# SpO_Sensor.net
KiCad netlist of a schematic drawn in Altium Designer
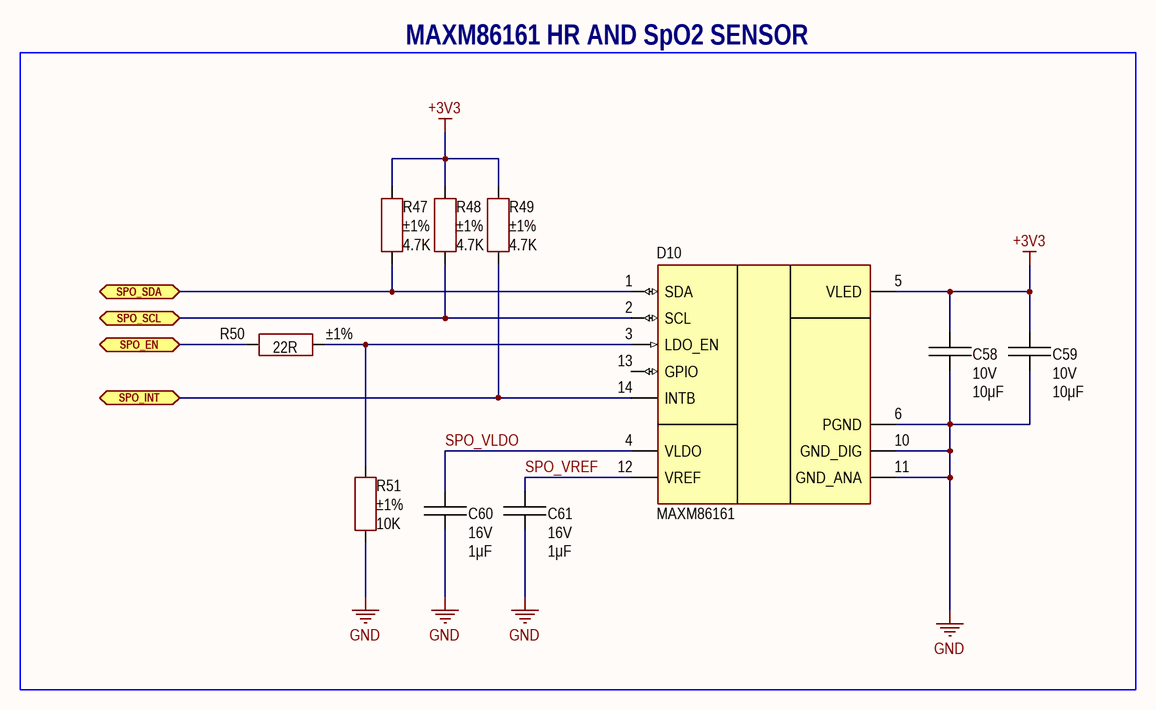
[diagram p0: SpO_Sensor.SchDoc]

(export (version "E")
  (design (tool "Eeschema 10.0.6"))
  (components
    (comp (ref "C58")
      (value "10μF")
      (footprint "CAP: 0805")
      (description "10 µF ±10% 10V Ceramic Capacitor X7R 0805 (2012 Metric)")
      (fields
        (field (name "MANUFACTURER") "Yageo")
        (field (name "PARTNUMBER") "CC0805KFX7R6BB106")
        (field (name "VOLTAGE") "10V")
      )
      (libsource (lib "capacitor") (part "Ceramic_0805"))
    )
    (comp (ref "C59")
      (value "10μF")
      (footprint "CAP: 0805")
      (description "10 µF ±10% 10V Ceramic Capacitor X7R 0805 (2012 Metric)")
      (fields
        (field (name "MANUFACTURER") "Yageo")
        (field (name "PARTNUMBER") "CC0805KFX7R6BB106")
        (field (name "VOLTAGE") "10V")
      )
      (libsource (lib "capacitor") (part "Ceramic_0805"))
    )
    (comp (ref "C60")
      (value "1μF")
      (footprint "CAP: 0805")
      (description "1 µF ±10% 16V Ceramic Capacitor X7R 0805 (2012 Metric)")
      (fields
        (field (name "MANUFACTURER") "Yageo")
        (field (name "PARTNUMBER") "CC0805KKX7R7BB105")
        (field (name "VOLTAGE") "16V")
      )
      (libsource (lib "capacitor") (part "Ceramic_0805"))
    )
    (comp (ref "C61")
      (value "1μF")
      (footprint "CAP: 0805")
      (description "1 µF ±10% 16V Ceramic Capacitor X7R 0805 (2012 Metric)")
      (fields
        (field (name "MANUFACTURER") "Yageo")
        (field (name "PARTNUMBER") "CC0805KKX7R7BB105")
        (field (name "VOLTAGE") "16V")
      )
      (libsource (lib "capacitor") (part "Ceramic_0805"))
    )
    (comp (ref "D10")
      (value "~")
      (footprint "IC: 14-OLGA")
      (description "HR and SpO2 sensor")
      (fields
        (field (name "MANUFACTURER") "Maxim Integrated")
        (field (name "VALUEMANUFACTURERPARTNUMBER") "IC HR and SpO2 sensor, HR and SpO2 sensor, , , , -40°C..+85°C, 14-OLGA")
        (field (name "PARTNUMBER") "MAXM86161")
      )
      (libsource (lib "MyLib") (part "MAXM86161"))
    )
    (comp (ref "R47")
      (value "4.7K")
      (footprint "RES: 0805")
      (description "4.7 kOhms ±5% 0.125W, 1/8W Chip Resistor 0805 (2012 Metric) Moisture Resistant Thick Film")
      (fields
        (field (name "MANUFACTURER") "Yageo")
        (field (name "PARTNUMBER") "RC0805JR-074K7L")
        (field (name "TOLERANCE") "±1%")
      )
      (libsource (lib "resistor") (part "Resistor_0805"))
    )
    (comp (ref "R48")
      (value "4.7K")
      (footprint "RES: 0805")
      (description "4.7 kOhms ±5% 0.125W, 1/8W Chip Resistor 0805 (2012 Metric) Moisture Resistant Thick Film")
      (fields
        (field (name "MANUFACTURER") "Yageo")
        (field (name "PARTNUMBER") "RC0805JR-074K7L")
        (field (name "TOLERANCE") "±1%")
      )
      (libsource (lib "resistor") (part "Resistor_0805"))
    )
    (comp (ref "R49")
      (value "4.7K")
      (footprint "RES: 0805")
      (description "4.7 kOhms ±5% 0.125W, 1/8W Chip Resistor 0805 (2012 Metric) Moisture Resistant Thick Film")
      (fields
        (field (name "MANUFACTURER") "Yageo")
        (field (name "PARTNUMBER") "RC0805JR-074K7L")
        (field (name "TOLERANCE") "±1%")
      )
      (libsource (lib "resistor") (part "Resistor_0805"))
    )
    (comp (ref "R50")
      (value "22R")
      (footprint "RES: 0805")
      (description "22 Ohms ±1% 0.125W, 1/8W Chip Resistor 0805 (2012 Metric) Moisture Resistant Thick Film")
      (fields
        (field (name "MANUFACTURER") "Yageo")
        (field (name "PARTNUMBER") "RC0805FR-0722RL")
        (field (name "TOLERANCE") "±1%")
      )
      (libsource (lib "") (part "Resistor_0805_1"))
    )
    (comp (ref "R51")
      (value "10K")
      (footprint "RES: 0805")
      (description "10 kOhms ±1% 0.125W, 1/8W Chip Resistor 0805 (2012 Metric) Moisture Resistant Thick Film")
      (fields
        (field (name "MANUFACTURER") "Yageo")
        (field (name "PARTNUMBER") "RC0805FR-0710KL")
        (field (name "TOLERANCE") "±1%")
      )
      (libsource (lib "resistor") (part "Resistor_0805"))
    )
  )
  (nets
    (net (code "1") (name "+3V3") (class "Default")
      (node (ref "C58") (pin "2") (pinfunction "2_2") (pintype "passive"))
      (node (ref "C59") (pin "2") (pinfunction "2_2") (pintype "passive"))
      (node (ref "D10") (pin "5") (pinfunction "VLED_5") (pintype "power_in"))
      (node (ref "R47") (pin "1") (pinfunction "1_1") (pintype "passive"))
      (node (ref "R48") (pin "1") (pinfunction "1_1") (pintype "passive"))
      (node (ref "R49") (pin "1") (pinfunction "1_1") (pintype "passive"))
    )
    (net (code "2") (name "/SPO_EN") (class "Default")
      (node (ref "R50") (pin "1") (pinfunction "1_1") (pintype "passive"))
    )
    (net (code "3") (name "/SPO_INT") (class "Default")
      (node (ref "D10") (pin "14") (pinfunction "INTB_14") (pintype "open_collector"))
      (node (ref "R49") (pin "2") (pinfunction "2_2") (pintype "passive"))
    )
    (net (code "4") (name "/SPO_SCL") (class "Default")
      (node (ref "D10") (pin "2") (pinfunction "SCL_2") (pintype "bidirectional"))
      (node (ref "R48") (pin "2") (pinfunction "2_2") (pintype "passive"))
    )
    (net (code "5") (name "/SPO_SDA") (class "Default")
      (node (ref "D10") (pin "1") (pinfunction "SDA_1") (pintype "bidirectional"))
      (node (ref "R47") (pin "2") (pinfunction "2_2") (pintype "passive"))
    )
    (net (code "6") (name "/SPO_VLDO") (class "Default")
      (node (ref "C60") (pin "2") (pinfunction "2_2") (pintype "passive"))
      (node (ref "D10") (pin "4") (pinfunction "VLDO_4") (pintype "power_in"))
    )
    (net (code "7") (name "/SPO_VREF") (class "Default")
      (node (ref "C61") (pin "2") (pinfunction "2_2") (pintype "passive"))
      (node (ref "D10") (pin "12") (pinfunction "VREF_12") (pintype "power_in"))
    )
    (net (code "8") (name "GND") (class "Default")
      (node (ref "C58") (pin "1") (pinfunction "1_1") (pintype "passive"))
      (node (ref "C59") (pin "1") (pinfunction "1_1") (pintype "passive"))
      (node (ref "C60") (pin "1") (pinfunction "1_1") (pintype "passive"))
      (node (ref "C61") (pin "1") (pinfunction "1_1") (pintype "passive"))
      (node (ref "D10") (pin "10") (pinfunction "GND_DIG_10") (pintype "power_in"))
      (node (ref "D10") (pin "11") (pinfunction "GND_ANA_11") (pintype "power_in"))
      (node (ref "D10") (pin "6") (pinfunction "PGND_6") (pintype "power_in"))
      (node (ref "R51") (pin "2") (pinfunction "2_2") (pintype "passive"))
    )
    (net (code "9") (name "Net-(D10-LDO_EN)") (class "Default")
      (node (ref "D10") (pin "3") (pinfunction "LDO_EN_3") (pintype "input"))
      (node (ref "R50") (pin "2") (pinfunction "2_2") (pintype "passive"))
      (node (ref "R51") (pin "1") (pinfunction "1_1") (pintype "passive"))
    )
    (net (code "10") (name "unconnected-(D10-GPIO-Pad13)") (class "Default")
      (node (ref "D10") (pin "13") (pinfunction "GPIO_13") (pintype "bidirectional"))
    )
  )
)
